# smart-plug.net
KiCad netlist of a schematic drawn in EAGLE
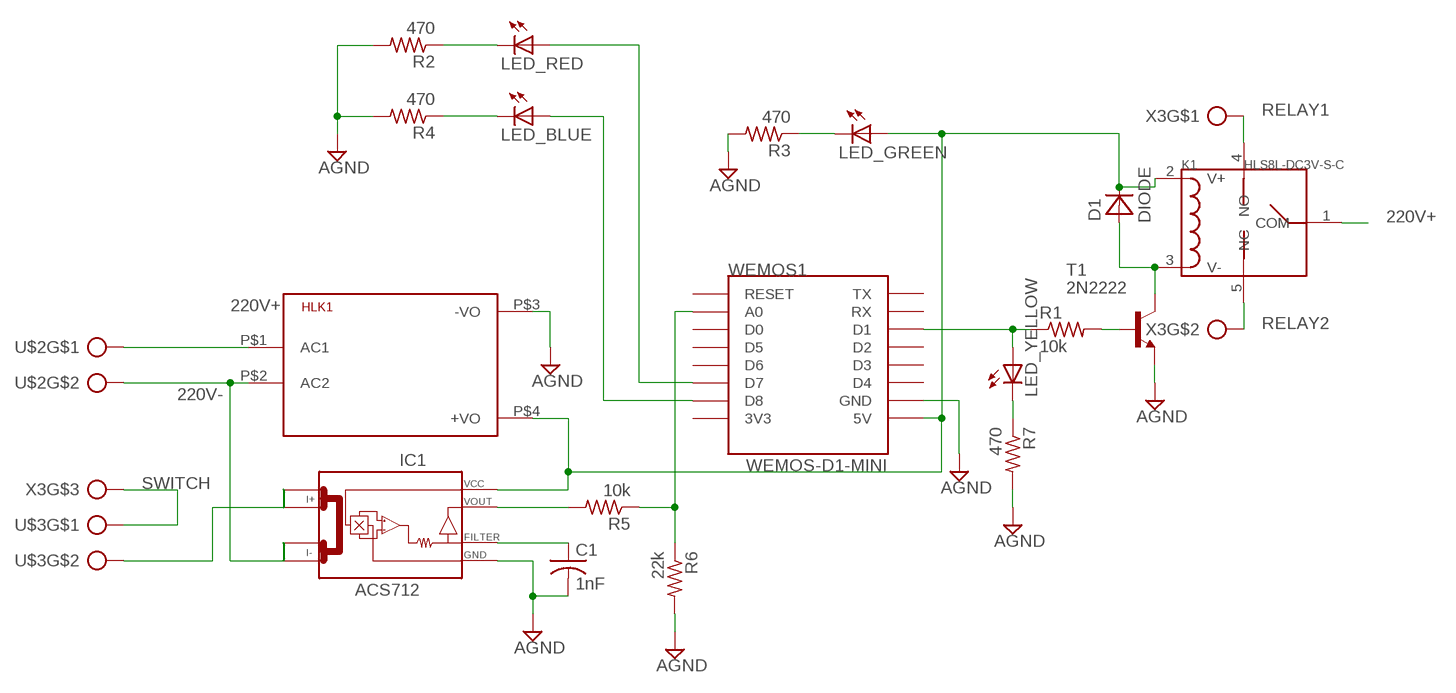
[diagram p0: schematic, sheet 1]

(export (version "E")
  (design (tool "Eeschema 10.0.6"))
  (components
    (comp (ref "C1")
      (value "1nF")
      (footprint "eagle-import:C1206")
      (libsource (lib "eagle-import") (part "C-USC1206"))
    )
    (comp (ref "D1")
      (value "DIODE")
      (footprint "eagle-import:DO41-10")
      (libsource (lib "eagle-import") (part "DIODE"))
    )
    (comp (ref "HLK1")
      (value "HLK-SUPPLY")
      (footprint "eagle-import:HLK-PM01")
      (libsource (lib "eagle-import") (part "HLK-SUPPLY"))
    )
    (comp (ref "IC1")
      (value "ACS712")
      (footprint "eagle-import:SO08")
      (libsource (lib "eagle-import") (part "ACS712"))
    )
    (comp (ref "K1")
      (value "HLS8L-DC3V-S-C")
      (footprint "eagle-import:REY5-19.0X15.0X15.0MM")
      (libsource (lib "eagle-import") (part "RELAY"))
    )
    (comp (ref "LED_BLUE")
      (value "LEDCHIP-LED0805")
      (footprint "eagle-import:CHIP-LED0805")
      (libsource (lib "eagle-import") (part "LEDCHIP-LED0805"))
    )
    (comp (ref "LED_GREEN")
      (value "LEDCHIP-LED0805")
      (footprint "eagle-import:CHIP-LED0805")
      (libsource (lib "eagle-import") (part "LEDCHIP-LED0805"))
    )
    (comp (ref "LED_RED")
      (value "LEDCHIP-LED0805")
      (footprint "eagle-import:CHIP-LED0805")
      (libsource (lib "eagle-import") (part "LEDCHIP-LED0805"))
    )
    (comp (ref "LED_YELLOW")
      (value "LEDCHIP-LED0805")
      (footprint "eagle-import:CHIP-LED0805")
      (libsource (lib "eagle-import") (part "LEDCHIP-LED0805"))
    )
    (comp (ref "R1")
      (value "10k")
      (footprint "eagle-import:R1206")
      (libsource (lib "eagle-import") (part "R-US_R1206"))
    )
    (comp (ref "R2")
      (value "470")
      (footprint "eagle-import:R1206")
      (libsource (lib "eagle-import") (part "R-US_R1206"))
    )
    (comp (ref "R3")
      (value "470")
      (footprint "eagle-import:R1206")
      (libsource (lib "eagle-import") (part "R-US_R1206"))
    )
    (comp (ref "R4")
      (value "470")
      (footprint "eagle-import:R1206")
      (libsource (lib "eagle-import") (part "R-US_R1206"))
    )
    (comp (ref "R5")
      (value "10k")
      (footprint "eagle-import:R1206")
      (libsource (lib "eagle-import") (part "R-US_R1206"))
    )
    (comp (ref "R6")
      (value "22k")
      (footprint "eagle-import:R1206")
      (libsource (lib "eagle-import") (part "R-US_R1206"))
    )
    (comp (ref "R7")
      (value "470")
      (footprint "eagle-import:R1206")
      (libsource (lib "eagle-import") (part "R-US_R1206"))
    )
    (comp (ref "T1")
      (value "2N2222")
      (footprint "eagle-import:TO92-EBC-OVAL")
      (libsource (lib "eagle-import") (part "2N2222"))
    )
    (comp (ref "U$2")
      (value "OUT-2PINS")
      (footprint "eagle-import:AK300_2")
      (libsource (lib "eagle-import") (part "OUT-2PINS"))
    )
    (comp (ref "U$3")
      (value "OUT-2PINS")
      (footprint "eagle-import:AK300_2")
      (libsource (lib "eagle-import") (part "OUT-2PINS"))
    )
    (comp (ref "WEMOS1")
      (value "WEMOS-D1-MINI")
      (footprint "eagle-import:WEMOS-D1-MINI")
      (libsource (lib "eagle-import") (part "WEMOS-D1-MINI"))
    )
    (comp (ref "X3")
      (value "OUT-3PINS")
      (footprint "eagle-import:AK300_3")
      (libsource (lib "eagle-import") (part "OUT-3PINS"))
    )
  )
  (nets
    (net (code "1") (name "/220V+") (class "Default")
      (node (ref "HLK1") (pin "P$1") (pinfunction "AC1_P$1") (pintype "bidirectional"))
      (node (ref "K1") (pin "1") (pinfunction "COM_1") (pintype "bidirectional"))
      (node (ref "U$2") (pin "1") (pinfunction "KL_1") (pintype "passive"))
    )
    (net (code "2") (name "/220V-") (class "Default")
      (node (ref "HLK1") (pin "P$2") (pinfunction "AC2_P$2") (pintype "bidirectional"))
      (node (ref "IC1") (pin "4") (pinfunction "I-_1_4") (pintype "bidirectional"))
      (node (ref "U$2") (pin "2") (pinfunction "KL_2") (pintype "passive"))
    )
    (net (code "3") (name "/RELAY1") (class "Default")
      (node (ref "K1") (pin "4") (pinfunction "NO_4") (pintype "bidirectional"))
      (node (ref "X3") (pin "1") (pinfunction "KL_1") (pintype "passive"))
    )
    (net (code "4") (name "/RELAY2") (class "Default")
      (node (ref "K1") (pin "5") (pinfunction "NC_5") (pintype "bidirectional"))
      (node (ref "X3") (pin "2") (pinfunction "KL_2") (pintype "passive"))
    )
    (net (code "5") (name "/SWITCH") (class "Default")
      (node (ref "U$3") (pin "1") (pinfunction "KL_1") (pintype "passive"))
      (node (ref "X3") (pin "3") (pinfunction "KL_3") (pintype "passive"))
    )
    (net (code "6") (name "AGND") (class "Default")
      (node (ref "C1") (pin "2") (pinfunction "2_2") (pintype "passive"))
      (node (ref "HLK1") (pin "P$3") (pinfunction "-VO_P$3") (pintype "bidirectional"))
      (node (ref "IC1") (pin "5") (pinfunction "GND_5") (pintype "power_in"))
      (node (ref "R2") (pin "2") (pinfunction "2_2") (pintype "passive"))
      (node (ref "R3") (pin "2") (pinfunction "2_2") (pintype "passive"))
      (node (ref "R4") (pin "2") (pinfunction "2_2") (pintype "passive"))
      (node (ref "R6") (pin "2") (pinfunction "2_2") (pintype "passive"))
      (node (ref "R7") (pin "2") (pinfunction "2_2") (pintype "passive"))
      (node (ref "T1") (pin "E") (pinfunction "E_E") (pintype "passive"))
      (node (ref "WEMOS1") (pin "GND") (pinfunction "GND_GND") (pintype "bidirectional"))
    )
    (net (code "7") (name "Net-(HLK1-+VO)") (class "Default")
      (node (ref "D1") (pin "C") (pinfunction "C_C") (pintype "passive"))
      (node (ref "HLK1") (pin "P$4") (pinfunction "+VO_P$4") (pintype "bidirectional"))
      (node (ref "IC1") (pin "8") (pinfunction "VCC_8") (pintype "power_in"))
      (node (ref "K1") (pin "2") (pinfunction "V+_2") (pintype "bidirectional"))
      (node (ref "LED_GREEN") (pin "A") (pinfunction "A_A") (pintype "passive"))
      (node (ref "WEMOS1") (pin "5V") (pinfunction "5V_5V") (pintype "bidirectional"))
    )
    (net (code "8") (name "Net-(IC1-FILTER)") (class "Default")
      (node (ref "C1") (pin "1") (pinfunction "1_1") (pintype "passive"))
      (node (ref "IC1") (pin "6") (pinfunction "FILTER_6") (pintype "bidirectional"))
    )
    (net (code "9") (name "Net-(IC1-I+_1)") (class "Default")
      (node (ref "IC1") (pin "2") (pinfunction "I+_1_2") (pintype "bidirectional"))
      (node (ref "U$3") (pin "2") (pinfunction "KL_2") (pintype "passive"))
    )
    (net (code "10") (name "Net-(IC1-VOUT)") (class "Default")
      (node (ref "IC1") (pin "7") (pinfunction "VOUT_7") (pintype "output"))
      (node (ref "R5") (pin "2") (pinfunction "2_2") (pintype "passive"))
    )
    (net (code "11") (name "Net-(K1-V-)") (class "Default")
      (node (ref "D1") (pin "A") (pinfunction "A_A") (pintype "passive"))
      (node (ref "K1") (pin "3") (pinfunction "V-_3") (pintype "bidirectional"))
      (node (ref "T1") (pin "C") (pinfunction "C_C") (pintype "passive"))
    )
    (net (code "12") (name "Net-(LED_BLUE-PadA)") (class "Default")
      (node (ref "LED_BLUE") (pin "A") (pinfunction "A_A") (pintype "passive"))
      (node (ref "WEMOS1") (pin "D8") (pinfunction "D8_D8") (pintype "bidirectional"))
    )
    (net (code "13") (name "Net-(LED_BLUE-PadC)") (class "Default")
      (node (ref "LED_BLUE") (pin "C") (pinfunction "C_C") (pintype "passive"))
      (node (ref "R4") (pin "1") (pinfunction "1_1") (pintype "passive"))
    )
    (net (code "14") (name "Net-(LED_GREEN-PadC)") (class "Default")
      (node (ref "LED_GREEN") (pin "C") (pinfunction "C_C") (pintype "passive"))
      (node (ref "R3") (pin "1") (pinfunction "1_1") (pintype "passive"))
    )
    (net (code "15") (name "Net-(LED_RED-PadA)") (class "Default")
      (node (ref "LED_RED") (pin "A") (pinfunction "A_A") (pintype "passive"))
      (node (ref "WEMOS1") (pin "D7") (pinfunction "D7_D7") (pintype "bidirectional"))
    )
    (net (code "16") (name "Net-(LED_RED-PadC)") (class "Default")
      (node (ref "LED_RED") (pin "C") (pinfunction "C_C") (pintype "passive"))
      (node (ref "R2") (pin "1") (pinfunction "1_1") (pintype "passive"))
    )
    (net (code "17") (name "Net-(LED_YELLOW-PadA)") (class "Default")
      (node (ref "LED_YELLOW") (pin "A") (pinfunction "A_A") (pintype "passive"))
      (node (ref "R1") (pin "1") (pinfunction "1_1") (pintype "passive"))
      (node (ref "WEMOS1") (pin "D1") (pinfunction "D1_D1") (pintype "bidirectional"))
    )
    (net (code "18") (name "Net-(LED_YELLOW-PadC)") (class "Default")
      (node (ref "LED_YELLOW") (pin "C") (pinfunction "C_C") (pintype "passive"))
      (node (ref "R7") (pin "1") (pinfunction "1_1") (pintype "passive"))
    )
    (net (code "19") (name "Net-(R1-Pad2)") (class "Default")
      (node (ref "R1") (pin "2") (pinfunction "2_2") (pintype "passive"))
      (node (ref "T1") (pin "B") (pinfunction "B_B") (pintype "passive"))
    )
    (net (code "20") (name "Net-(R5-Pad1)") (class "Default")
      (node (ref "R5") (pin "1") (pinfunction "1_1") (pintype "passive"))
      (node (ref "R6") (pin "1") (pinfunction "1_1") (pintype "passive"))
      (node (ref "WEMOS1") (pin "A0") (pinfunction "A0_A0") (pintype "bidirectional"))
    )
    (net (code "21") (name "unconnected-(IC1-I+_0-Pad1)") (class "Default")
      (node (ref "IC1") (pin "1") (pinfunction "I+_0_1") (pintype "bidirectional"))
    )
    (net (code "22") (name "unconnected-(IC1-I-_0-Pad3)") (class "Default")
      (node (ref "IC1") (pin "3") (pinfunction "I-_0_3") (pintype "bidirectional"))
    )
    (net (code "23") (name "unconnected-(WEMOS1-Pad3V3)") (class "Default")
      (node (ref "WEMOS1") (pin "3V3") (pinfunction "3V3_3V3") (pintype "bidirectional"))
    )
    (net (code "24") (name "unconnected-(WEMOS1-PadD0)") (class "Default")
      (node (ref "WEMOS1") (pin "D0") (pinfunction "D0_D0") (pintype "bidirectional"))
    )
    (net (code "25") (name "unconnected-(WEMOS1-PadD2)") (class "Default")
      (node (ref "WEMOS1") (pin "D2") (pinfunction "D2_D2") (pintype "bidirectional"))
    )
    (net (code "26") (name "unconnected-(WEMOS1-PadD3)") (class "Default")
      (node (ref "WEMOS1") (pin "D3") (pinfunction "D3_D3") (pintype "bidirectional"))
    )
    (net (code "27") (name "unconnected-(WEMOS1-PadD4)") (class "Default")
      (node (ref "WEMOS1") (pin "D4") (pinfunction "D4_D4") (pintype "bidirectional"))
    )
    (net (code "28") (name "unconnected-(WEMOS1-PadD5)") (class "Default")
      (node (ref "WEMOS1") (pin "D5") (pinfunction "D5_D5") (pintype "bidirectional"))
    )
    (net (code "29") (name "unconnected-(WEMOS1-PadD6)") (class "Default")
      (node (ref "WEMOS1") (pin "D6") (pinfunction "D6_D6") (pintype "bidirectional"))
    )
    (net (code "30") (name "unconnected-(WEMOS1-PadRESET)") (class "Default")
      (node (ref "WEMOS1") (pin "RESET") (pinfunction "RESET_RESET") (pintype "bidirectional"))
    )
    (net (code "31") (name "unconnected-(WEMOS1-PadRX)") (class "Default")
      (node (ref "WEMOS1") (pin "RX") (pinfunction "RX_RX") (pintype "bidirectional"))
    )
    (net (code "32") (name "unconnected-(WEMOS1-PadTX)") (class "Default")
      (node (ref "WEMOS1") (pin "TX") (pinfunction "TX_TX") (pintype "bidirectional"))
    )
  )
)
